# fet_level_shifter.net
KiCad netlist of a schematic drawn in EAGLE
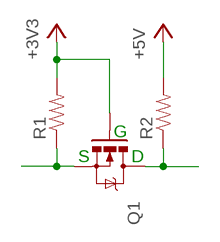
[diagram p0: schematic, sheet 1]

(export (version "E")
  (design (tool "Eeschema 10.0.6"))
  (components
    (comp (ref "Q1")
      (value "MOSFET-NCHANNEL2N7000")
      (footprint "eagle-import:TO-92")
      (libsource (lib "eagle-import") (part "MOSFET-NCHANNEL2N7000"))
    )
    (comp (ref "R1")
      (value "RESISTOR0402-RES")
      (footprint "eagle-import:0402-RES")
      (libsource (lib "eagle-import") (part "RESISTOR0402-RES"))
    )
    (comp (ref "R2")
      (value "RESISTOR0402-RES")
      (footprint "eagle-import:0402-RES")
      (libsource (lib "eagle-import") (part "RESISTOR0402-RES"))
    )
  )
  (nets
    (net (code "1") (name "+3V3") (class "Default")
      (node (ref "Q1") (pin "2") (pinfunction "G_2") (pintype "passive"))
      (node (ref "R1") (pin "2") (pinfunction "2_2") (pintype "passive"))
    )
    (net (code "2") (name "+5V") (class "Default")
      (node (ref "R2") (pin "2") (pinfunction "2_2") (pintype "passive"))
    )
    (net (code "3") (name "Net-(Q1-D)") (class "Default")
      (node (ref "Q1") (pin "3") (pinfunction "D_3") (pintype "passive"))
      (node (ref "R2") (pin "1") (pinfunction "1_1") (pintype "passive"))
    )
    (net (code "4") (name "Net-(Q1-S)") (class "Default")
      (node (ref "Q1") (pin "1") (pinfunction "S_1") (pintype "passive"))
      (node (ref "R1") (pin "1") (pinfunction "1_1") (pintype "passive"))
    )
  )
)
